# Esquema_V2_V1.net
KiCad netlist of a schematic drawn in Altium Designer
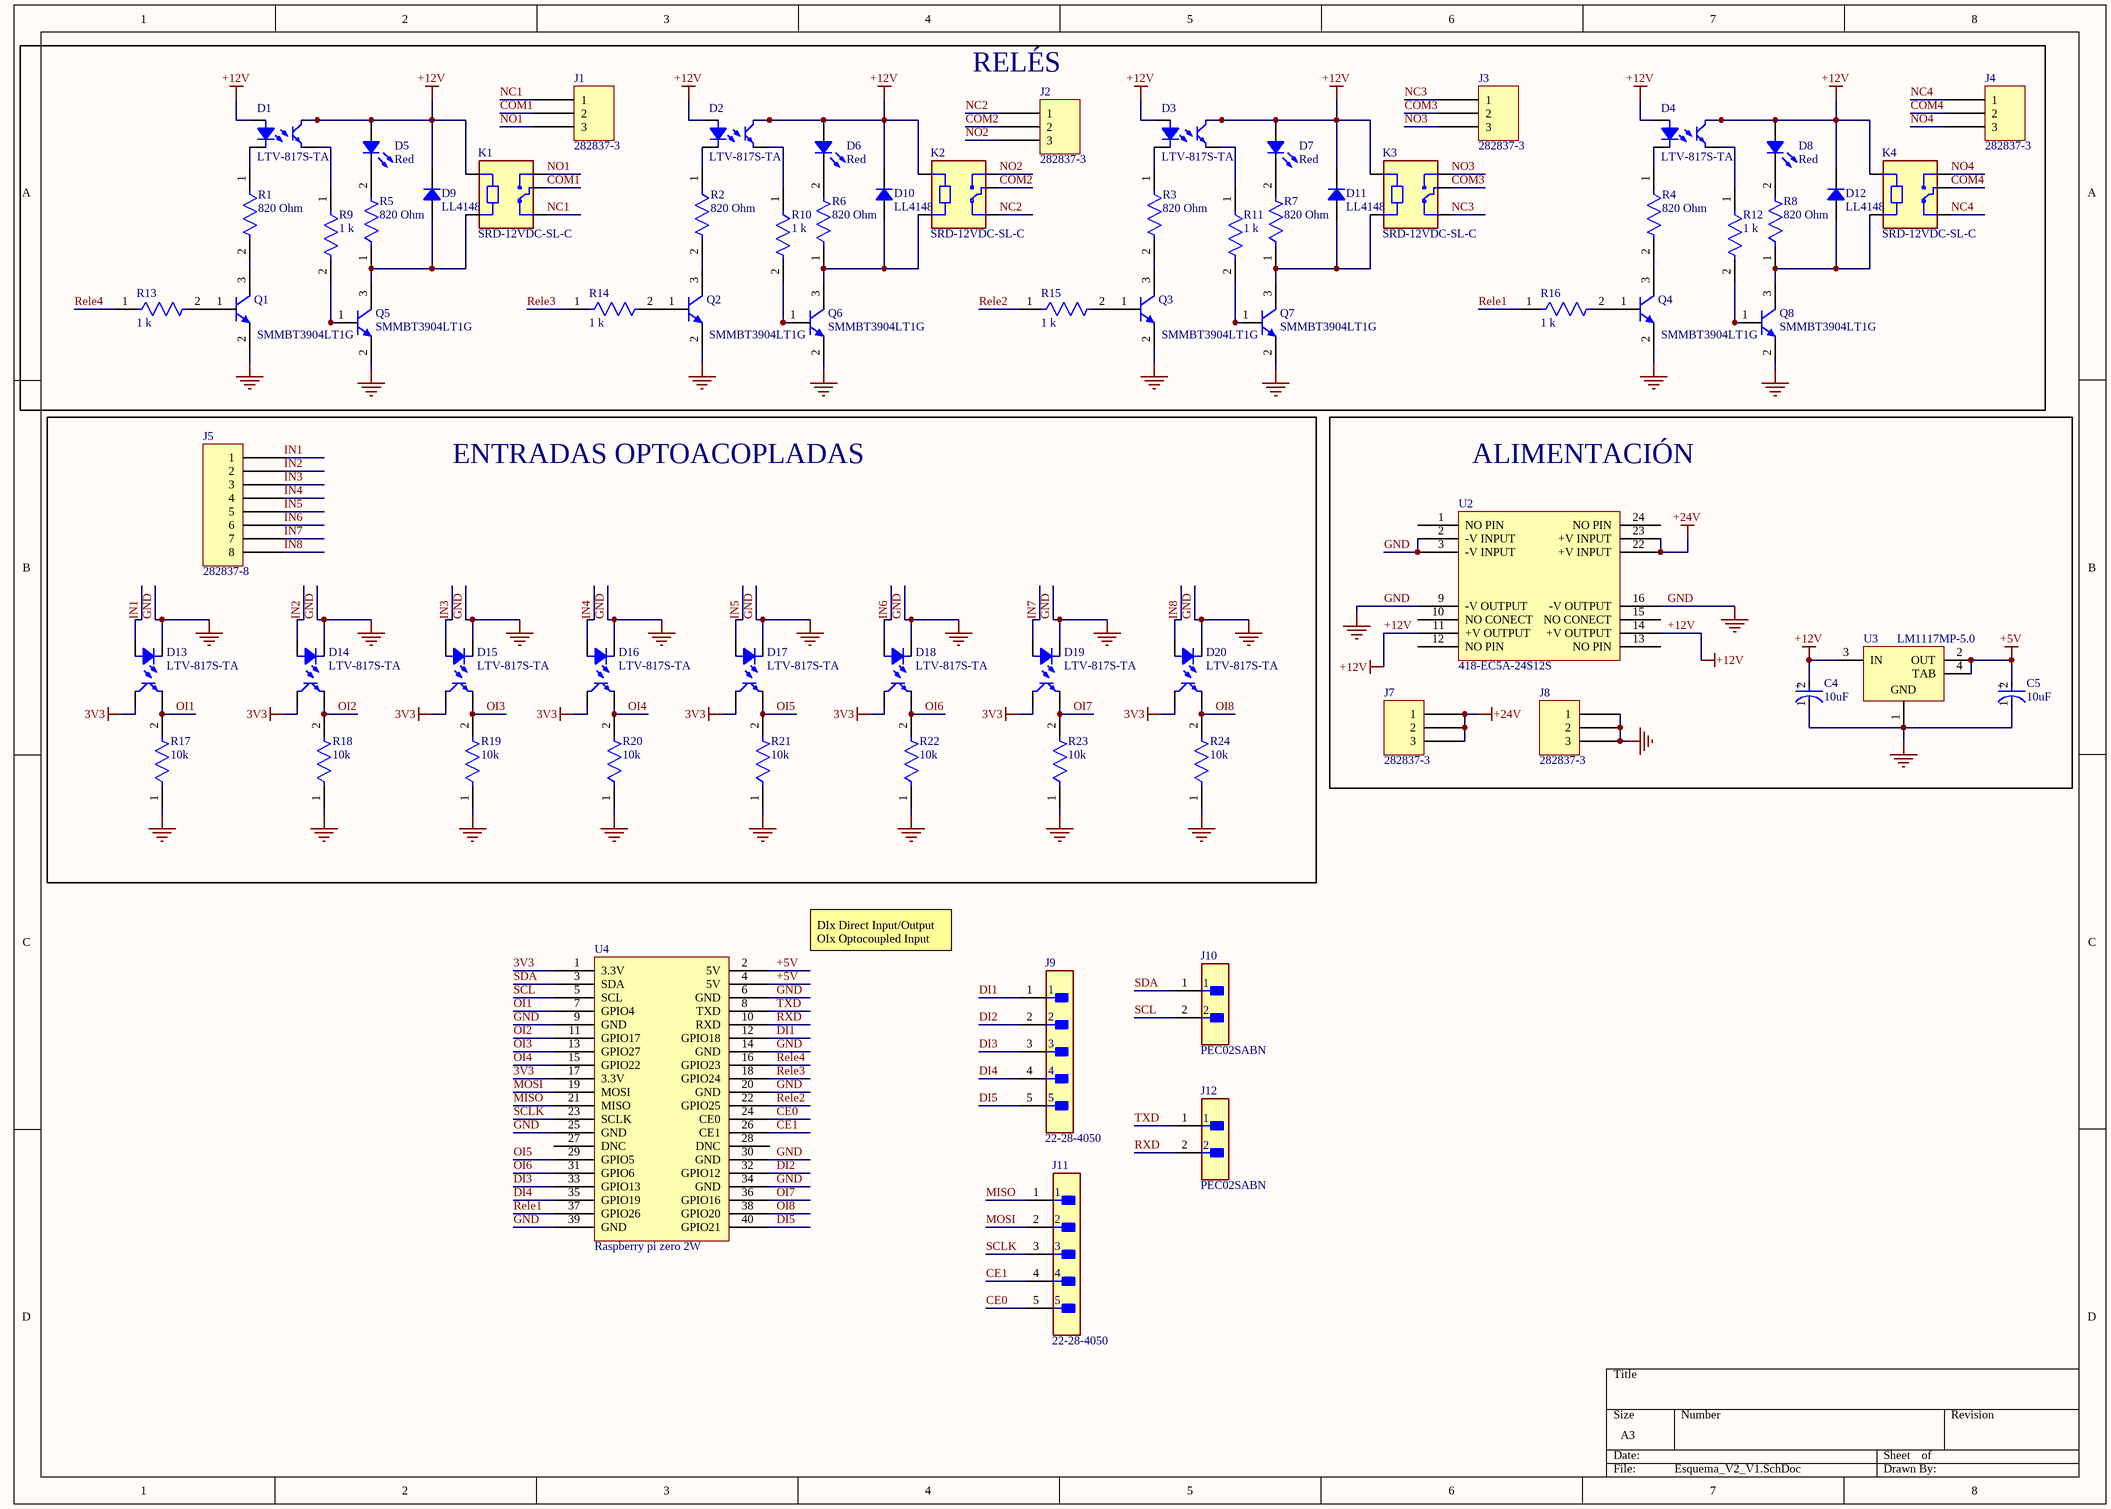
[diagram p0: Esquema_V2_V1.SchDoc]

(export (version "E")
  (design (tool "Eeschema 10.0.6"))
  (components
    (comp (ref "C4")
      (value "10uF")
      (footprint "FP-TAJA-MFG")
      (description "TAJA106M010RNJ 10uF 10V  ±20% 3Ω 1206  SMD Tantalum Capacitor")
      (fields (field (name "TOLERANCE") "20%") (field (name "VOLTAGE") "10V"))
      (libsource (lib "Altium Content Vault") (part "203bc49f2ac43e59fd269a8c329ed05"))
    )
    (comp (ref "C5")
      (value "10uF")
      (footprint "FP-TAJA-MFG")
      (description "TAJA106M010RNJ 10uF 10V  ±20% 3Ω 1206  SMD Tantalum Capacitor")
      (fields (field (name "TOLERANCE") "20%") (field (name "VOLTAGE") "10V"))
      (libsource (lib "Altium Content Vault") (part "203bc49f2ac43e59fd269a8c329ed05"))
    )
    (comp (ref "D1")
      (value "LTV-817S-TA")
      (footprint "LITEON LTV-817")
      (description "OPTOISOLATR 5KV TRANSISTOR 4-SMD")
      (fields (field (name "MANUFACTURER") "Lite-On Inc."))
      (libsource (lib "Celestial Altium Library - altium_library") (part "Optoisolator"))
    )
    (comp (ref "D2")
      (value "LTV-817S-TA")
      (footprint "LITEON LTV-817")
      (description "OPTOISOLATR 5KV TRANSISTOR 4-SMD")
      (fields (field (name "MANUFACTURER") "Lite-On Inc."))
      (libsource (lib "Celestial Altium Library - altium_library") (part "Optoisolator"))
    )
    (comp (ref "D3")
      (value "LTV-817S-TA")
      (footprint "LITEON LTV-817")
      (description "OPTOISOLATR 5KV TRANSISTOR 4-SMD")
      (fields (field (name "MANUFACTURER") "Lite-On Inc."))
      (libsource (lib "Celestial Altium Library - altium_library") (part "Optoisolator"))
    )
    (comp (ref "D4")
      (value "LTV-817S-TA")
      (footprint "LITEON LTV-817")
      (description "OPTOISOLATR 5KV TRANSISTOR 4-SMD")
      (fields (field (name "MANUFACTURER") "Lite-On Inc."))
      (libsource (lib "Celestial Altium Library - altium_library") (part "Optoisolator"))
    )
    (comp (ref "D5")
      (value "Red")
      (footprint "LED 1206_3216 RED")
      (description "LED RED CLEAR SMD")
      (fields (field (name "PART NUMBER") "LTST-C150KAKT") (field (name "MANUFACTURER") "Lite-On Inc."))
      (libsource (lib "Celestial Altium Library - altium_library") (part "LED"))
    )
    (comp (ref "D6")
      (value "Red")
      (footprint "LED 1206_3216 RED")
      (description "LED RED CLEAR SMD")
      (fields (field (name "PART NUMBER") "LTST-C150KAKT") (field (name "MANUFACTURER") "Lite-On Inc."))
      (libsource (lib "Celestial Altium Library - altium_library") (part "LED"))
    )
    (comp (ref "D7")
      (value "Red")
      (footprint "LED 1206_3216 RED")
      (description "LED RED CLEAR SMD")
      (fields (field (name "PART NUMBER") "LTST-C150KAKT") (field (name "MANUFACTURER") "Lite-On Inc."))
      (libsource (lib "Celestial Altium Library - altium_library") (part "LED"))
    )
    (comp (ref "D8")
      (value "Red")
      (footprint "LED 1206_3216 RED")
      (description "LED RED CLEAR SMD")
      (fields (field (name "PART NUMBER") "LTST-C150KAKT") (field (name "MANUFACTURER") "Lite-On Inc."))
      (libsource (lib "Celestial Altium Library - altium_library") (part "LED"))
    )
    (comp (ref "D9")
      (value "LL4148")
      (footprint "SOD-80 MiniMELF")
      (description "DIODE GEN PURP 100V 200MA SOD80")
      (fields (field (name "MANUFACTURER") "ON Semiconductor"))
      (libsource (lib "Celestial Altium Library - altium_library") (part "Diode"))
    )
    (comp (ref "D10")
      (value "LL4148")
      (footprint "SOD-80 MiniMELF")
      (description "DIODE GEN PURP 100V 200MA SOD80")
      (fields (field (name "MANUFACTURER") "ON Semiconductor"))
      (libsource (lib "Celestial Altium Library - altium_library") (part "Diode"))
    )
    (comp (ref "D11")
      (value "LL4148")
      (footprint "SOD-80 MiniMELF")
      (description "DIODE GEN PURP 100V 200MA SOD80")
      (fields (field (name "MANUFACTURER") "ON Semiconductor"))
      (libsource (lib "Celestial Altium Library - altium_library") (part "Diode"))
    )
    (comp (ref "D12")
      (value "LL4148")
      (footprint "SOD-80 MiniMELF")
      (description "DIODE GEN PURP 100V 200MA SOD80")
      (fields (field (name "MANUFACTURER") "ON Semiconductor"))
      (libsource (lib "Celestial Altium Library - altium_library") (part "Diode"))
    )
    (comp (ref "D13")
      (value "LTV-817S-TA")
      (footprint "LITEON LTV-817")
      (description "OPTOISOLATR 5KV TRANSISTOR 4-SMD")
      (fields (field (name "MANUFACTURER") "Lite-On Inc."))
      (libsource (lib "Celestial Altium Library - altium_library") (part "Optoisolator"))
    )
    (comp (ref "D14")
      (value "LTV-817S-TA")
      (footprint "LITEON LTV-817")
      (description "OPTOISOLATR 5KV TRANSISTOR 4-SMD")
      (fields (field (name "MANUFACTURER") "Lite-On Inc."))
      (libsource (lib "Celestial Altium Library - altium_library") (part "Optoisolator"))
    )
    (comp (ref "D15")
      (value "LTV-817S-TA")
      (footprint "LITEON LTV-817")
      (description "OPTOISOLATR 5KV TRANSISTOR 4-SMD")
      (fields (field (name "MANUFACTURER") "Lite-On Inc."))
      (libsource (lib "Celestial Altium Library - altium_library") (part "Optoisolator"))
    )
    (comp (ref "D16")
      (value "LTV-817S-TA")
      (footprint "LITEON LTV-817")
      (description "OPTOISOLATR 5KV TRANSISTOR 4-SMD")
      (fields (field (name "MANUFACTURER") "Lite-On Inc."))
      (libsource (lib "Celestial Altium Library - altium_library") (part "Optoisolator"))
    )
    (comp (ref "D17")
      (value "LTV-817S-TA")
      (footprint "LITEON LTV-817")
      (description "OPTOISOLATR 5KV TRANSISTOR 4-SMD")
      (fields (field (name "MANUFACTURER") "Lite-On Inc."))
      (libsource (lib "Celestial Altium Library - altium_library") (part "Optoisolator"))
    )
    (comp (ref "D18")
      (value "LTV-817S-TA")
      (footprint "LITEON LTV-817")
      (description "OPTOISOLATR 5KV TRANSISTOR 4-SMD")
      (fields (field (name "MANUFACTURER") "Lite-On Inc."))
      (libsource (lib "Celestial Altium Library - altium_library") (part "Optoisolator"))
    )
    (comp (ref "D19")
      (value "LTV-817S-TA")
      (footprint "LITEON LTV-817")
      (description "OPTOISOLATR 5KV TRANSISTOR 4-SMD")
      (fields (field (name "MANUFACTURER") "Lite-On Inc."))
      (libsource (lib "Celestial Altium Library - altium_library") (part "Optoisolator"))
    )
    (comp (ref "D20")
      (value "LTV-817S-TA")
      (footprint "LITEON LTV-817")
      (description "OPTOISOLATR 5KV TRANSISTOR 4-SMD")
      (fields (field (name "MANUFACTURER") "Lite-On Inc."))
      (libsource (lib "Celestial Altium Library - altium_library") (part "Optoisolator"))
    )
    (comp (ref "J1")
      (value "282837-3")
      (footprint "TE 282837-3")
      (description "TERM BLK 3P SIDE ENT 5.08MM PCB")
      (fields (field (name "MANUFACTURER") "TE Connectivity AMP Connectors") (field (name "VOLTAGE") "300 V"))
      (libsource (lib "Celestial Altium Library - altium_library") (part "3 Pin"))
    )
    (comp (ref "J2")
      (value "282837-3")
      (footprint "TE 282837-3")
      (description "TERM BLK 3P SIDE ENT 5.08MM PCB")
      (fields (field (name "MANUFACTURER") "TE Connectivity AMP Connectors") (field (name "VOLTAGE") "300 V"))
      (libsource (lib "Celestial Altium Library - altium_library") (part "3 Pin"))
    )
    (comp (ref "J3")
      (value "282837-3")
      (footprint "TE 282837-3")
      (description "TERM BLK 3P SIDE ENT 5.08MM PCB")
      (fields (field (name "MANUFACTURER") "TE Connectivity AMP Connectors") (field (name "VOLTAGE") "300 V"))
      (libsource (lib "Celestial Altium Library - altium_library") (part "3 Pin"))
    )
    (comp (ref "J4")
      (value "282837-3")
      (footprint "TE 282837-3")
      (description "TERM BLK 3P SIDE ENT 5.08MM PCB")
      (fields (field (name "MANUFACTURER") "TE Connectivity AMP Connectors") (field (name "VOLTAGE") "300 V"))
      (libsource (lib "Celestial Altium Library - altium_library") (part "3 Pin"))
    )
    (comp (ref "J5")
      (value "282837-8")
      (footprint "TE 282837-8")
      (description "TERM BLK 8P SIDE ENT 5.08MM PCB")
      (fields (field (name "MANUFACTURER") "TE Connectivity AMP Connectors") (field (name "VOLTAGE") "300 V"))
      (libsource (lib "Celestial Altium Library - altium_library") (part "8 Pin"))
    )
    (comp (ref "J7")
      (value "282837-3")
      (footprint "TE 282837-3")
      (description "TERM BLK 3P SIDE ENT 5.08MM PCB")
      (fields (field (name "MANUFACTURER") "TE Connectivity AMP Connectors") (field (name "VOLTAGE") "300 V"))
      (libsource (lib "") (part "3 Pin_1"))
    )
    (comp (ref "J8")
      (value "282837-3")
      (footprint "TE 282837-3")
      (description "TERM BLK 3P SIDE ENT 5.08MM PCB")
      (fields (field (name "MANUFACTURER") "TE Connectivity AMP Connectors") (field (name "VOLTAGE") "300 V"))
      (libsource (lib "") (part "3 Pin_1"))
    )
    (comp (ref "J9")
      (value "22-28-4050")
      (footprint "FP-22-28-4050-MFG")
      (libsource (lib "Altium Content Vault") (part "bf93c07fd2649a848d0ec8585582aab"))
    )
    (comp (ref "J10")
      (value "PEC02SABN")
      (footprint "FP-PEC02SABN-MFG")
      (description "CONN HEADER VERT 2POS 2.54MM")
      (libsource (lib "Altium Content Vault") (part "3bc925449376181038e59eaffc5286c"))
    )
    (comp (ref "J11")
      (value "22-28-4050")
      (footprint "FP-22-28-4050-MFG")
      (libsource (lib "Altium Content Vault") (part "bf93c07fd2649a848d0ec8585582aab"))
    )
    (comp (ref "J12")
      (value "PEC02SABN")
      (footprint "FP-PEC02SABN-MFG")
      (description "CONN HEADER VERT 2POS 2.54MM")
      (libsource (lib "Altium Content Vault") (part "3bc925449376181038e59eaffc5286c"))
    )
    (comp (ref "K1")
      (value "SRD-12VDC-SL-C")
      (footprint "RELAY_SRD-05VDC-SL-C")
      (fields (field (name "MF") "Songle Relay") (field (name "MP") "SRD-05VDC-SL-C"))
      (libsource (lib "SRD-05VDC-SL-C") (part "SRD-05VDC-SL-C"))
    )
    (comp (ref "K2")
      (value "SRD-12VDC-SL-C")
      (footprint "RELAY_SRD-05VDC-SL-C")
      (fields (field (name "MF") "Songle Relay") (field (name "MP") "SRD-05VDC-SL-C"))
      (libsource (lib "SRD-05VDC-SL-C") (part "SRD-05VDC-SL-C"))
    )
    (comp (ref "K3")
      (value "SRD-12VDC-SL-C")
      (footprint "RELAY_SRD-05VDC-SL-C")
      (fields (field (name "MF") "Songle Relay") (field (name "MP") "SRD-05VDC-SL-C"))
      (libsource (lib "SRD-05VDC-SL-C") (part "SRD-05VDC-SL-C"))
    )
    (comp (ref "K4")
      (value "SRD-12VDC-SL-C")
      (footprint "RELAY_SRD-05VDC-SL-C")
      (fields (field (name "MF") "Songle Relay") (field (name "MP") "SRD-05VDC-SL-C"))
      (libsource (lib "SRD-05VDC-SL-C") (part "SRD-05VDC-SL-C"))
    )
    (comp (ref "Q1")
      (value "SMMBT3904LT1G")
      (footprint "ONSC-SOT-23-3-318-08_V")
      (description "General Purpose Transistor, NPN Silicon, 3-Pin SOT-23, Pb-Free, Tape and Reel")
      (fields (field (name "MANUFACTURER") "On Semiconductor"))
      (libsource (lib "Altium Content Vault") (part "ONSC-NPN-B1E2C3-3"))
    )
    (comp (ref "Q2")
      (value "SMMBT3904LT1G")
      (footprint "ONSC-SOT-23-3-318-08_V")
      (description "General Purpose Transistor, NPN Silicon, 3-Pin SOT-23, Pb-Free, Tape and Reel")
      (fields (field (name "MANUFACTURER") "On Semiconductor"))
      (libsource (lib "Altium Content Vault") (part "ONSC-NPN-B1E2C3-3"))
    )
    (comp (ref "Q3")
      (value "SMMBT3904LT1G")
      (footprint "ONSC-SOT-23-3-318-08_V")
      (description "General Purpose Transistor, NPN Silicon, 3-Pin SOT-23, Pb-Free, Tape and Reel")
      (fields (field (name "MANUFACTURER") "On Semiconductor"))
      (libsource (lib "Altium Content Vault") (part "ONSC-NPN-B1E2C3-3"))
    )
    (comp (ref "Q4")
      (value "SMMBT3904LT1G")
      (footprint "ONSC-SOT-23-3-318-08_V")
      (description "General Purpose Transistor, NPN Silicon, 3-Pin SOT-23, Pb-Free, Tape and Reel")
      (fields (field (name "MANUFACTURER") "On Semiconductor"))
      (libsource (lib "Altium Content Vault") (part "ONSC-NPN-B1E2C3-3"))
    )
    (comp (ref "Q5")
      (value "SMMBT3904LT1G")
      (footprint "ONSC-SOT-23-3-318-08_V")
      (description "General Purpose Transistor, NPN Silicon, 3-Pin SOT-23, Pb-Free, Tape and Reel")
      (fields (field (name "MANUFACTURER") "On Semiconductor"))
      (libsource (lib "Altium Content Vault") (part "ONSC-NPN-B1E2C3-3"))
    )
    (comp (ref "Q6")
      (value "SMMBT3904LT1G")
      (footprint "ONSC-SOT-23-3-318-08_V")
      (description "General Purpose Transistor, NPN Silicon, 3-Pin SOT-23, Pb-Free, Tape and Reel")
      (fields (field (name "MANUFACTURER") "On Semiconductor"))
      (libsource (lib "Altium Content Vault") (part "ONSC-NPN-B1E2C3-3"))
    )
    (comp (ref "Q7")
      (value "SMMBT3904LT1G")
      (footprint "ONSC-SOT-23-3-318-08_V")
      (description "General Purpose Transistor, NPN Silicon, 3-Pin SOT-23, Pb-Free, Tape and Reel")
      (fields (field (name "MANUFACTURER") "On Semiconductor"))
      (libsource (lib "Altium Content Vault") (part "ONSC-NPN-B1E2C3-3"))
    )
    (comp (ref "Q8")
      (value "SMMBT3904LT1G")
      (footprint "ONSC-SOT-23-3-318-08_V")
      (description "General Purpose Transistor, NPN Silicon, 3-Pin SOT-23, Pb-Free, Tape and Reel")
      (fields (field (name "MANUFACTURER") "On Semiconductor"))
      (libsource (lib "Altium Content Vault") (part "ONSC-NPN-B1E2C3-3"))
    )
    (comp (ref "R1")
      (value "820 Ohm")
      (footprint "FP-CRCW0603-HPe3-MFG")
      (description "RES Thick Film, 820Ω, 1%, 0.33W, 100ppm/°C, 0603")
      (fields (field (name "TOLERANCE") "1%"))
      (libsource (lib "Altium Content Vault") (part "1029c3af85768c4190bb7ad29bc67b5"))
    )
    (comp (ref "R2")
      (value "820 Ohm")
      (footprint "FP-CRCW0603-HPe3-MFG")
      (description "RES Thick Film, 820Ω, 1%, 0.33W, 100ppm/°C, 0603")
      (fields (field (name "TOLERANCE") "1%"))
      (libsource (lib "Altium Content Vault") (part "1029c3af85768c4190bb7ad29bc67b5"))
    )
    (comp (ref "R3")
      (value "820 Ohm")
      (footprint "FP-CRCW0603-HPe3-MFG")
      (description "RES Thick Film, 820Ω, 1%, 0.33W, 100ppm/°C, 0603")
      (fields (field (name "TOLERANCE") "1%"))
      (libsource (lib "Altium Content Vault") (part "1029c3af85768c4190bb7ad29bc67b5"))
    )
    (comp (ref "R4")
      (value "820 Ohm")
      (footprint "FP-CRCW0603-HPe3-MFG")
      (description "RES Thick Film, 820Ω, 1%, 0.33W, 100ppm/°C, 0603")
      (fields (field (name "TOLERANCE") "1%"))
      (libsource (lib "Altium Content Vault") (part "1029c3af85768c4190bb7ad29bc67b5"))
    )
    (comp (ref "R5")
      (value "820 Ohm")
      (footprint "FP-CRCW0603-HPe3-MFG")
      (description "RES Thick Film, 820Ω, 1%, 0.33W, 100ppm/°C, 0603")
      (fields (field (name "TOLERANCE") "1%"))
      (libsource (lib "Altium Content Vault") (part "1029c3af85768c4190bb7ad29bc67b5"))
    )
    (comp (ref "R6")
      (value "820 Ohm")
      (footprint "FP-CRCW0603-HPe3-MFG")
      (description "RES Thick Film, 820Ω, 1%, 0.33W, 100ppm/°C, 0603")
      (fields (field (name "TOLERANCE") "1%"))
      (libsource (lib "Altium Content Vault") (part "1029c3af85768c4190bb7ad29bc67b5"))
    )
    (comp (ref "R7")
      (value "820 Ohm")
      (footprint "FP-CRCW0603-HPe3-MFG")
      (description "RES Thick Film, 820Ω, 1%, 0.33W, 100ppm/°C, 0603")
      (fields (field (name "TOLERANCE") "1%"))
      (libsource (lib "Altium Content Vault") (part "1029c3af85768c4190bb7ad29bc67b5"))
    )
    (comp (ref "R8")
      (value "820 Ohm")
      (footprint "FP-CRCW0603-HPe3-MFG")
      (description "RES Thick Film, 820Ω, 1%, 0.33W, 100ppm/°C, 0603")
      (fields (field (name "TOLERANCE") "1%"))
      (libsource (lib "Altium Content Vault") (part "1029c3af85768c4190bb7ad29bc67b5"))
    )
    (comp (ref "R9")
      (value "1 k")
      (footprint "FP-MCT0603-IPC_C")
      (description "MCT0603PD1001DP500 RES SMD 100 OHM 1% 1/8W 0603")
      (fields (field (name "TOLERANCE") "0.5%"))
      (libsource (lib "Altium Content Vault") (part "1029c3af85768c4190bb7ad29bc67b5"))
    )
    (comp (ref "R10")
      (value "1 k")
      (footprint "FP-MCT0603-IPC_C")
      (description "MCT0603PD1001DP500 RES SMD 100 OHM 1% 1/8W 0603")
      (fields (field (name "TOLERANCE") "0.5%"))
      (libsource (lib "Altium Content Vault") (part "1029c3af85768c4190bb7ad29bc67b5"))
    )
    (comp (ref "R11")
      (value "1 k")
      (footprint "FP-MCT0603-IPC_C")
      (description "MCT0603PD1001DP500 RES SMD 100 OHM 1% 1/8W 0603")
      (fields (field (name "TOLERANCE") "0.5%"))
      (libsource (lib "Altium Content Vault") (part "1029c3af85768c4190bb7ad29bc67b5"))
    )
    (comp (ref "R12")
      (value "1 k")
      (footprint "FP-MCT0603-IPC_C")
      (description "MCT0603PD1001DP500 RES SMD 100 OHM 1% 1/8W 0603")
      (fields (field (name "TOLERANCE") "0.5%"))
      (libsource (lib "Altium Content Vault") (part "1029c3af85768c4190bb7ad29bc67b5"))
    )
    (comp (ref "R13")
      (value "1 k")
      (footprint "FP-MCT0603-IPC_C")
      (description "MCT0603PD1001DP500 RES SMD 100 OHM 1% 1/8W 0603")
      (fields (field (name "TOLERANCE") "0.5%"))
      (libsource (lib "Altium Content Vault") (part "1029c3af85768c4190bb7ad29bc67b5"))
    )
    (comp (ref "R14")
      (value "1 k")
      (footprint "FP-MCT0603-IPC_C")
      (description "MCT0603PD1001DP500 RES SMD 100 OHM 1% 1/8W 0603")
      (fields (field (name "TOLERANCE") "0.5%"))
      (libsource (lib "Altium Content Vault") (part "1029c3af85768c4190bb7ad29bc67b5"))
    )
    (comp (ref "R15")
      (value "1 k")
      (footprint "FP-MCT0603-IPC_C")
      (description "MCT0603PD1001DP500 RES SMD 100 OHM 1% 1/8W 0603")
      (fields (field (name "TOLERANCE") "0.5%"))
      (libsource (lib "Altium Content Vault") (part "1029c3af85768c4190bb7ad29bc67b5"))
    )
    (comp (ref "R16")
      (value "1 k")
      (footprint "FP-MCT0603-IPC_C")
      (description "MCT0603PD1001DP500 RES SMD 100 OHM 1% 1/8W 0603")
      (fields (field (name "TOLERANCE") "0.5%"))
      (libsource (lib "Altium Content Vault") (part "1029c3af85768c4190bb7ad29bc67b5"))
    )
    (comp (ref "R17")
      (value "10k")
      (footprint "FP-MCT0603-IPC_B")
      (description "MCT0603MD1002BP100 RES SMD 10k OHM 1% 1/8W 0603")
      (fields (field (name "TOLERANCE") "0.1%"))
      (libsource (lib "Altium Content Vault") (part "1029c3af85768c4190bb7ad29bc67b5"))
    )
    (comp (ref "R18")
      (value "10k")
      (footprint "FP-MCT0603-IPC_B")
      (description "MCT0603MD1002BP100 RES SMD 10k OHM 1% 1/8W 0603")
      (fields (field (name "TOLERANCE") "0.1%"))
      (libsource (lib "Altium Content Vault") (part "1029c3af85768c4190bb7ad29bc67b5"))
    )
    (comp (ref "R19")
      (value "10k")
      (footprint "FP-MCT0603-IPC_B")
      (description "MCT0603MD1002BP100 RES SMD 10k OHM 1% 1/8W 0603")
      (fields (field (name "TOLERANCE") "0.1%"))
      (libsource (lib "Altium Content Vault") (part "1029c3af85768c4190bb7ad29bc67b5"))
    )
    (comp (ref "R20")
      (value "10k")
      (footprint "FP-MCT0603-IPC_B")
      (description "MCT0603MD1002BP100 RES SMD 10k OHM 1% 1/8W 0603")
      (fields (field (name "TOLERANCE") "0.1%"))
      (libsource (lib "Altium Content Vault") (part "1029c3af85768c4190bb7ad29bc67b5"))
    )
    (comp (ref "R21")
      (value "10k")
      (footprint "FP-MCT0603-IPC_B")
      (description "MCT0603MD1002BP100 RES SMD 10k OHM 1% 1/8W 0603")
      (fields (field (name "TOLERANCE") "0.1%"))
      (libsource (lib "Altium Content Vault") (part "1029c3af85768c4190bb7ad29bc67b5"))
    )
    (comp (ref "R22")
      (value "10k")
      (footprint "FP-MCT0603-IPC_B")
      (description "MCT0603MD1002BP100 RES SMD 10k OHM 1% 1/8W 0603")
      (fields (field (name "TOLERANCE") "0.1%"))
      (libsource (lib "Altium Content Vault") (part "1029c3af85768c4190bb7ad29bc67b5"))
    )
    (comp (ref "R23")
      (value "10k")
      (footprint "FP-MCT0603-IPC_B")
      (description "MCT0603MD1002BP100 RES SMD 10k OHM 1% 1/8W 0603")
      (fields (field (name "TOLERANCE") "0.1%"))
      (libsource (lib "Altium Content Vault") (part "1029c3af85768c4190bb7ad29bc67b5"))
    )
    (comp (ref "R24")
      (value "10k")
      (footprint "FP-MCT0603-IPC_B")
      (description "MCT0603MD1002BP100 RES SMD 10k OHM 1% 1/8W 0603")
      (fields (field (name "TOLERANCE") "0.1%"))
      (libsource (lib "Altium Content Vault") (part "1029c3af85768c4190bb7ad29bc67b5"))
    )
    (comp (ref "U2")
      (value "418-EC5A-24S12S")
      (footprint "418-EC5A-24S12S")
      (libsource (lib "Raspberry") (part "418-EC5A-24S12S"))
    )
    (comp (ref "U3")
      (value "LM1117MP-5.0")
      (footprint "MP04A_N")
      (description "800mA Low-Dropout Linear Regulator, 4-pin SOT-223")
      (fields (field (name "MANUFACTURER") "National Semiconductor"))
      (libsource (lib "Altium Content Vault") (part "PM-REG-LM1086-SOT4"))
    )
    (comp (ref "U4")
      (value "Raspberry pi zero 2W")
      (footprint "PCBComponent_1")
      (libsource (lib "Raspberry") (part "Raspberry pi zero 2W"))
    )
  )
  (nets
    (net (code "1") (name "+5V") (class "Default")
      (node (ref "C5") (pin "2") (pinfunction "A_2") (pintype "passive"))
      (node (ref "U3") (pin "2") (pinfunction "OUT_2") (pintype "power_in"))
      (node (ref "U3") (pin "4") (pinfunction "TAB_4") (pintype "power_in"))
      (node (ref "U4") (pin "2") (pinfunction "5V_2") (pintype "passive"))
      (node (ref "U4") (pin "4") (pinfunction "5V_4") (pintype "passive"))
    )
    (net (code "2") (name "+12V") (class "Default")
      (node (ref "C4") (pin "2") (pinfunction "A_2") (pintype "passive"))
      (node (ref "D1") (pin "1") (pinfunction "1_1") (pintype "passive"))
      (node (ref "D1") (pin "4") (pinfunction "4_4") (pintype "passive"))
      (node (ref "D10") (pin "2") (pinfunction "2_2") (pintype "passive"))
      (node (ref "D11") (pin "2") (pinfunction "2_2") (pintype "passive"))
      (node (ref "D12") (pin "2") (pinfunction "2_2") (pintype "passive"))
      (node (ref "D2") (pin "1") (pinfunction "1_1") (pintype "passive"))
      (node (ref "D2") (pin "4") (pinfunction "4_4") (pintype "passive"))
      (node (ref "D3") (pin "1") (pinfunction "1_1") (pintype "passive"))
      (node (ref "D3") (pin "4") (pinfunction "4_4") (pintype "passive"))
      (node (ref "D4") (pin "1") (pinfunction "1_1") (pintype "passive"))
      (node (ref "D4") (pin "4") (pinfunction "4_4") (pintype "passive"))
      (node (ref "D5") (pin "1") (pinfunction "1_1") (pintype "passive"))
      (node (ref "D6") (pin "1") (pinfunction "1_1") (pintype "passive"))
      (node (ref "D7") (pin "1") (pinfunction "1_1") (pintype "passive"))
      (node (ref "D8") (pin "1") (pinfunction "1_1") (pintype "passive"))
      (node (ref "D9") (pin "2") (pinfunction "2_2") (pintype "passive"))
      (node (ref "K1") (pin "A1") (pinfunction "A1_A1") (pintype "passive"))
      (node (ref "K2") (pin "A1") (pinfunction "A1_A1") (pintype "passive"))
      (node (ref "K3") (pin "A1") (pinfunction "A1_A1") (pintype "passive"))
      (node (ref "K4") (pin "A1") (pinfunction "A1_A1") (pintype "passive"))
      (node (ref "U2") (pin "11") (pinfunction "+V_OUTPUT_11") (pintype "passive"))
      (node (ref "U2") (pin "14") (pinfunction "+V_OUTPUT_14") (pintype "passive"))
      (node (ref "U3") (pin "3") (pinfunction "IN_3") (pintype "power_in"))
    )
    (net (code "3") (name "+24V") (class "Default")
      (node (ref "J7") (pin "1") (pinfunction "1_1") (pintype "passive"))
      (node (ref "J7") (pin "2") (pinfunction "2_2") (pintype "passive"))
      (node (ref "J7") (pin "3") (pinfunction "3_3") (pintype "passive"))
      (node (ref "U2") (pin "22") (pinfunction "+V_INPUT_22") (pintype "passive"))
      (node (ref "U2") (pin "23") (pinfunction "+V_INPUT_23") (pintype "passive"))
    )
    (net (code "4") (name "/CE0") (class "Default")
      (node (ref "J11") (pin "5") (pinfunction "5_5") (pintype "passive"))
      (node (ref "U4") (pin "24") (pinfunction "CE0_24") (pintype "passive"))
    )
    (net (code "5") (name "/CE1") (class "Default")
      (node (ref "J11") (pin "4") (pinfunction "4_4") (pintype "passive"))
      (node (ref "U4") (pin "26") (pinfunction "CE1_26") (pintype "passive"))
    )
    (net (code "6") (name "/COM1") (class "Default")
      (node (ref "J1") (pin "2") (pinfunction "2_2") (pintype "passive"))
      (node (ref "K1") (pin "COM") (pinfunction "COM_COM") (pintype "passive"))
    )
    (net (code "7") (name "/COM2") (class "Default")
      (node (ref "J2") (pin "2") (pinfunction "2_2") (pintype "passive"))
      (node (ref "K2") (pin "COM") (pinfunction "COM_COM") (pintype "passive"))
    )
    (net (code "8") (name "/COM3") (class "Default")
      (node (ref "J3") (pin "2") (pinfunction "2_2") (pintype "passive"))
      (node (ref "K3") (pin "COM") (pinfunction "COM_COM") (pintype "passive"))
    )
    (net (code "9") (name "/COM4") (class "Default")
      (node (ref "J4") (pin "2") (pinfunction "2_2") (pintype "passive"))
      (node (ref "K4") (pin "COM") (pinfunction "COM_COM") (pintype "passive"))
    )
    (net (code "10") (name "/DI1") (class "Default")
      (node (ref "J9") (pin "1") (pinfunction "1_1") (pintype "passive"))
      (node (ref "U4") (pin "12") (pinfunction "GPIO18_12") (pintype "passive"))
    )
    (net (code "11") (name "/DI2") (class "Default")
      (node (ref "J9") (pin "2") (pinfunction "2_2") (pintype "passive"))
      (node (ref "U4") (pin "32") (pinfunction "GPIO12_32") (pintype "passive"))
    )
    (net (code "12") (name "/DI3") (class "Default")
      (node (ref "J9") (pin "3") (pinfunction "3_3") (pintype "passive"))
      (node (ref "U4") (pin "33") (pinfunction "GPIO13_33") (pintype "passive"))
    )
    (net (code "13") (name "/DI4") (class "Default")
      (node (ref "J9") (pin "4") (pinfunction "4_4") (pintype "passive"))
      (node (ref "U4") (pin "35") (pinfunction "GPIO19_35") (pintype "passive"))
    )
    (net (code "14") (name "/DI5") (class "Default")
      (node (ref "J9") (pin "5") (pinfunction "5_5") (pintype "passive"))
      (node (ref "U4") (pin "40") (pinfunction "GPIO21_40") (pintype "passive"))
    )
    (net (code "15") (name "/IN1") (class "Default")
      (node (ref "D13") (pin "1") (pinfunction "1_1") (pintype "passive"))
      (node (ref "J5") (pin "1") (pinfunction "1_1") (pintype "passive"))
    )
    (net (code "16") (name "/IN2") (class "Default")
      (node (ref "D14") (pin "1") (pinfunction "1_1") (pintype "passive"))
      (node (ref "J5") (pin "2") (pinfunction "2_2") (pintype "passive"))
    )
    (net (code "17") (name "/IN3") (class "Default")
      (node (ref "D15") (pin "1") (pinfunction "1_1") (pintype "passive"))
      (node (ref "J5") (pin "3") (pinfunction "3_3") (pintype "passive"))
    )
    (net (code "18") (name "/IN4") (class "Default")
      (node (ref "D16") (pin "1") (pinfunction "1_1") (pintype "passive"))
      (node (ref "J5") (pin "4") (pinfunction "4_4") (pintype "passive"))
    )
    (net (code "19") (name "/IN5") (class "Default")
      (node (ref "D17") (pin "1") (pinfunction "1_1") (pintype "passive"))
      (node (ref "J5") (pin "5") (pinfunction "5_5") (pintype "passive"))
    )
    (net (code "20") (name "/IN6") (class "Default")
      (node (ref "D18") (pin "1") (pinfunction "1_1") (pintype "passive"))
      (node (ref "J5") (pin "6") (pinfunction "6_6") (pintype "passive"))
    )
    (net (code "21") (name "/IN7") (class "Default")
      (node (ref "D19") (pin "1") (pinfunction "1_1") (pintype "passive"))
      (node (ref "J5") (pin "7") (pinfunction "7_7") (pintype "passive"))
    )
    (net (code "22") (name "/IN8") (class "Default")
      (node (ref "D20") (pin "1") (pinfunction "1_1") (pintype "passive"))
      (node (ref "J5") (pin "8") (pinfunction "8_8") (pintype "passive"))
    )
    (net (code "23") (name "/MISO") (class "Default")
      (node (ref "J11") (pin "1") (pinfunction "1_1") (pintype "passive"))
      (node (ref "U4") (pin "21") (pinfunction "MISO_21") (pintype "passive"))
    )
    (net (code "24") (name "/MOSI") (class "Default")
      (node (ref "J11") (pin "2") (pinfunction "2_2") (pintype "passive"))
      (node (ref "U4") (pin "19") (pinfunction "MOSI_19") (pintype "passive"))
    )
    (net (code "25") (name "/NC1") (class "Default")
      (node (ref "J1") (pin "1") (pinfunction "1_1") (pintype "passive"))
      (node (ref "K1") (pin "NC") (pinfunction "NC_NC") (pintype "passive"))
    )
    (net (code "26") (name "/NC2") (class "Default")
      (node (ref "J2") (pin "1") (pinfunction "1_1") (pintype "passive"))
      (node (ref "K2") (pin "NC") (pinfunction "NC_NC") (pintype "passive"))
    )
    (net (code "27") (name "/NC3") (class "Default")
      (node (ref "J3") (pin "1") (pinfunction "1_1") (pintype "passive"))
      (node (ref "K3") (pin "NC") (pinfunction "NC_NC") (pintype "passive"))
    )
    (net (code "28") (name "/NC4") (class "Default")
      (node (ref "J4") (pin "1") (pinfunction "1_1") (pintype "passive"))
      (node (ref "K4") (pin "NC") (pinfunction "NC_NC") (pintype "passive"))
    )
    (net (code "29") (name "/NO1") (class "Default")
      (node (ref "J1") (pin "3") (pinfunction "3_3") (pintype "passive"))
      (node (ref "K1") (pin "NO") (pinfunction "NO_NO") (pintype "passive"))
    )
    (net (code "30") (name "/NO2") (class "Default")
      (node (ref "J2") (pin "3") (pinfunction "3_3") (pintype "passive"))
      (node (ref "K2") (pin "NO") (pinfunction "NO_NO") (pintype "passive"))
    )
    (net (code "31") (name "/NO3") (class "Default")
      (node (ref "J3") (pin "3") (pinfunction "3_3") (pintype "passive"))
      (node (ref "K3") (pin "NO") (pinfunction "NO_NO") (pintype "passive"))
    )
    (net (code "32") (name "/NO4") (class "Default")
      (node (ref "J4") (pin "3") (pinfunction "3_3") (pintype "passive"))
      (node (ref "K4") (pin "NO") (pinfunction "NO_NO") (pintype "passive"))
    )
    (net (code "33") (name "/OI1") (class "Default")
      (node (ref "D13") (pin "3") (pinfunction "3_3") (pintype "passive"))
      (node (ref "R17") (pin "2") (pinfunction "2_2") (pintype "passive"))
      (node (ref "U4") (pin "7") (pinfunction "GPIO4_7") (pintype "passive"))
    )
    (net (code "34") (name "/OI2") (class "Default")
      (node (ref "D14") (pin "3") (pinfunction "3_3") (pintype "passive"))
      (node (ref "R18") (pin "2") (pinfunction "2_2") (pintype "passive"))
      (node (ref "U4") (pin "11") (pinfunction "GPIO17_11") (pintype "passive"))
    )
    (net (code "35") (name "/OI3") (class "Default")
      (node (ref "D15") (pin "3") (pinfunction "3_3") (pintype "passive"))
      (node (ref "R19") (pin "2") (pinfunction "2_2") (pintype "passive"))
      (node (ref "U4") (pin "13") (pinfunction "GPIO27_13") (pintype "passive"))
    )
    (net (code "36") (name "/OI4") (class "Default")
      (node (ref "D16") (pin "3") (pinfunction "3_3") (pintype "passive"))
      (node (ref "R20") (pin "2") (pinfunction "2_2") (pintype "passive"))
      (node (ref "U4") (pin "15") (pinfunction "GPIO22_15") (pintype "passive"))
    )
    (net (code "37") (name "/OI5") (class "Default")
      (node (ref "D17") (pin "3") (pinfunction "3_3") (pintype "passive"))
      (node (ref "R21") (pin "2") (pinfunction "2_2") (pintype "passive"))
      (node (ref "U4") (pin "29") (pinfunction "GPIO5_29") (pintype "passive"))
    )
    (net (code "38") (name "/OI6") (class "Default")
      (node (ref "D18") (pin "3") (pinfunction "3_3") (pintype "passive"))
      (node (ref "R22") (pin "2") (pinfunction "2_2") (pintype "passive"))
      (node (ref "U4") (pin "31") (pinfunction "GPIO6_31") (pintype "passive"))
    )
    (net (code "39") (name "/OI7") (class "Default")
      (node (ref "D19") (pin "3") (pinfunction "3_3") (pintype "passive"))
      (node (ref "R23") (pin "2") (pinfunction "2_2") (pintype "passive"))
      (node (ref "U4") (pin "36") (pinfunction "GPIO16_36") (pintype "passive"))
    )
    (net (code "40") (name "/OI8") (class "Default")
      (node (ref "D20") (pin "3") (pinfunction "3_3") (pintype "passive"))
      (node (ref "R24") (pin "2") (pinfunction "2_2") (pintype "passive"))
      (node (ref "U4") (pin "38") (pinfunction "GPIO20_38") (pintype "passive"))
    )
    (net (code "41") (name "/RXD") (class "Default")
      (node (ref "J12") (pin "2") (pinfunction "2_2") (pintype "passive"))
      (node (ref "U4") (pin "10") (pinfunction "RXD_10") (pintype "passive"))
    )
    (net (code "42") (name "/Rele1") (class "Default")
      (node (ref "R16") (pin "1") (pinfunction "1_1") (pintype "passive"))
      (node (ref "U4") (pin "37") (pinfunction "GPIO26_37") (pintype "passive"))
    )
    (net (code "43") (name "/Rele2") (class "Default")
      (node (ref "R15") (pin "1") (pinfunction "1_1") (pintype "passive"))
      (node (ref "U4") (pin "22") (pinfunction "GPIO25_22") (pintype "passive"))
    )
    (net (code "44") (name "/Rele3") (class "Default")
      (node (ref "R14") (pin "1") (pinfunction "1_1") (pintype "passive"))
      (node (ref "U4") (pin "18") (pinfunction "GPIO24_18") (pintype "passive"))
    )
    (net (code "45") (name "/Rele4") (class "Default")
      (node (ref "R13") (pin "1") (pinfunction "1_1") (pintype "passive"))
      (node (ref "U4") (pin "16") (pinfunction "GPIO23_16") (pintype "passive"))
    )
    (net (code "46") (name "/SCL") (class "Default")
      (node (ref "J10") (pin "2") (pinfunction "2_2") (pintype "passive"))
      (node (ref "U4") (pin "5") (pinfunction "SCL_5") (pintype "passive"))
    )
    (net (code "47") (name "/SCLK") (class "Default")
      (node (ref "J11") (pin "3") (pinfunction "3_3") (pintype "passive"))
      (node (ref "U4") (pin "23") (pinfunction "SCLK_23") (pintype "passive"))
    )
    (net (code "48") (name "/SDA") (class "Default")
      (node (ref "J10") (pin "1") (pinfunction "1_1") (pintype "passive"))
      (node (ref "U4") (pin "3") (pinfunction "SDA_3") (pintype "passive"))
    )
    (net (code "49") (name "/TXD") (class "Default")
      (node (ref "J12") (pin "1") (pinfunction "1_1") (pintype "passive"))
      (node (ref "U4") (pin "8") (pinfunction "TXD_8") (pintype "passive"))
    )
    (net (code "50") (name "3V3") (class "Default")
      (node (ref "D13") (pin "4") (pinfunction "4_4") (pintype "passive"))
      (node (ref "D14") (pin "4") (pinfunction "4_4") (pintype "passive"))
      (node (ref "D15") (pin "4") (pinfunction "4_4") (pintype "passive"))
      (node (ref "D16") (pin "4") (pinfunction "4_4") (pintype "passive"))
      (node (ref "D17") (pin "4") (pinfunction "4_4") (pintype "passive"))
      (node (ref "D18") (pin "4") (pinfunction "4_4") (pintype "passive"))
      (node (ref "D19") (pin "4") (pinfunction "4_4") (pintype "passive"))
      (node (ref "D20") (pin "4") (pinfunction "4_4") (pintype "passive"))
      (node (ref "U4") (pin "1") (pinfunction "3.3V_1") (pintype "passive"))
      (node (ref "U4") (pin "17") (pinfunction "3.3V_17") (pintype "passive"))
    )
    (net (code "51") (name "GND") (class "Default")
      (node (ref "C4") (pin "1") (pinfunction "C_1") (pintype "passive"))
      (node (ref "C5") (pin "1") (pinfunction "C_1") (pintype "passive"))
      (node (ref "D13") (pin "2") (pinfunction "2_2") (pintype "passive"))
      (node (ref "D14") (pin "2") (pinfunction "2_2") (pintype "passive"))
      (node (ref "D15") (pin "2") (pinfunction "2_2") (pintype "passive"))
      (node (ref "D16") (pin "2") (pinfunction "2_2") (pintype "passive"))
      (node (ref "D17") (pin "2") (pinfunction "2_2") (pintype "passive"))
      (node (ref "D18") (pin "2") (pinfunction "2_2") (pintype "passive"))
      (node (ref "D19") (pin "2") (pinfunction "2_2") (pintype "passive"))
      (node (ref "D20") (pin "2") (pinfunction "2_2") (pintype "passive"))
      (node (ref "J8") (pin "1") (pinfunction "1_1") (pintype "passive"))
      (node (ref "J8") (pin "2") (pinfunction "2_2") (pintype "passive"))
      (node (ref "J8") (pin "3") (pinfunction "3_3") (pintype "passive"))
      (node (ref "Q1") (pin "2") (pinfunction "E_2") (pintype "passive"))
      (node (ref "Q2") (pin "2") (pinfunction "E_2") (pintype "passive"))
      (node (ref "Q3") (pin "2") (pinfunction "E_2") (pintype "passive"))
      (node (ref "Q4") (pin "2") (pinfunction "E_2") (pintype "passive"))
      (node (ref "Q5") (pin "2") (pinfunction "E_2") (pintype "passive"))
      (node (ref "Q6") (pin "2") (pinfunction "E_2") (pintype "passive"))
      (node (ref "Q7") (pin "2") (pinfunction "E_2") (pintype "passive"))
      (node (ref "Q8") (pin "2") (pinfunction "E_2") (pintype "passive"))
      (node (ref "R17") (pin "1") (pinfunction "1_1") (pintype "passive"))
      (node (ref "R18") (pin "1") (pinfunction "1_1") (pintype "passive"))
      (node (ref "R19") (pin "1") (pinfunction "1_1") (pintype "passive"))
      (node (ref "R20") (pin "1") (pinfunction "1_1") (pintype "passive"))
      (node (ref "R21") (pin "1") (pinfunction "1_1") (pintype "passive"))
      (node (ref "R22") (pin "1") (pinfunction "1_1") (pintype "passive"))
      (node (ref "R23") (pin "1") (pinfunction "1_1") (pintype "passive"))
      (node (ref "R24") (pin "1") (pinfunction "1_1") (pintype "passive"))
      (node (ref "U2") (pin "16") (pinfunction "-V_OUTPUT_16") (pintype "passive"))
      (node (ref "U2") (pin "2") (pinfunction "-V_INPUT_2") (pintype "passive"))
      (node (ref "U2") (pin "3") (pinfunction "-V_INPUT_3") (pintype "passive"))
      (node (ref "U2") (pin "9") (pinfunction "-V_OUTPUT_9") (pintype "passive"))
      (node (ref "U3") (pin "1") (pinfunction "GND_1") (pintype "power_in"))
      (node (ref "U4") (pin "14") (pinfunction "GND_14") (pintype "passive"))
      (node (ref "U4") (pin "20") (pinfunction "GND_20") (pintype "passive"))
      (node (ref "U4") (pin "25") (pinfunction "GND_25") (pintype "passive"))
      (node (ref "U4") (pin "30") (pinfunction "GND_30") (pintype "passive"))
      (node (ref "U4") (pin "34") (pinfunction "GND_34") (pintype "passive"))
      (node (ref "U4") (pin "39") (pinfunction "GND_39") (pintype "passive"))
      (node (ref "U4") (pin "6") (pinfunction "GND_6") (pintype "passive"))
      (node (ref "U4") (pin "9") (pinfunction "GND_9") (pintype "passive"))
    )
    (net (code "52") (name "Net-(D1-Pad2)") (class "Default")
      (node (ref "D1") (pin "2") (pinfunction "2_2") (pintype "passive"))
      (node (ref "R1") (pin "1") (pinfunction "1_1") (pintype "passive"))
    )
    (net (code "53") (name "Net-(D1-Pad3)") (class "Default")
      (node (ref "D1") (pin "3") (pinfunction "3_3") (pintype "passive"))
      (node (ref "R9") (pin "1") (pinfunction "1_1") (pintype "passive"))
    )
    (net (code "54") (name "Net-(D2-Pad2)") (class "Default")
      (node (ref "D2") (pin "2") (pinfunction "2_2") (pintype "passive"))
      (node (ref "R2") (pin "1") (pinfunction "1_1") (pintype "passive"))
    )
    (net (code "55") (name "Net-(D2-Pad3)") (class "Default")
      (node (ref "D2") (pin "3") (pinfunction "3_3") (pintype "passive"))
      (node (ref "R10") (pin "1") (pinfunction "1_1") (pintype "passive"))
    )
    (net (code "56") (name "Net-(D3-Pad2)") (class "Default")
      (node (ref "D3") (pin "2") (pinfunction "2_2") (pintype "passive"))
      (node (ref "R3") (pin "1") (pinfunction "1_1") (pintype "passive"))
    )
    (net (code "57") (name "Net-(D3-Pad3)") (class "Default")
      (node (ref "D3") (pin "3") (pinfunction "3_3") (pintype "passive"))
      (node (ref "R11") (pin "1") (pinfunction "1_1") (pintype "passive"))
    )
    (net (code "58") (name "Net-(D4-Pad2)") (class "Default")
      (node (ref "D4") (pin "2") (pinfunction "2_2") (pintype "passive"))
      (node (ref "R4") (pin "1") (pinfunction "1_1") (pintype "passive"))
    )
    (net (code "59") (name "Net-(D4-Pad3)") (class "Default")
      (node (ref "D4") (pin "3") (pinfunction "3_3") (pintype "passive"))
      (node (ref "R12") (pin "1") (pinfunction "1_1") (pintype "passive"))
    )
    (net (code "60") (name "Net-(D5-Pad2)") (class "Default")
      (node (ref "D5") (pin "2") (pinfunction "2_2") (pintype "passive"))
      (node (ref "R5") (pin "2") (pinfunction "2_2") (pintype "passive"))
    )
    (net (code "61") (name "Net-(D6-Pad2)") (class "Default")
      (node (ref "D6") (pin "2") (pinfunction "2_2") (pintype "passive"))
      (node (ref "R6") (pin "2") (pinfunction "2_2") (pintype "passive"))
    )
    (net (code "62") (name "Net-(D7-Pad2)") (class "Default")
      (node (ref "D7") (pin "2") (pinfunction "2_2") (pintype "passive"))
      (node (ref "R7") (pin "2") (pinfunction "2_2") (pintype "passive"))
    )
    (net (code "63") (name "Net-(D8-Pad2)") (class "Default")
      (node (ref "D8") (pin "2") (pinfunction "2_2") (pintype "passive"))
      (node (ref "R8") (pin "2") (pinfunction "2_2") (pintype "passive"))
    )
    (net (code "64") (name "Net-(Q1-B)") (class "Default")
      (node (ref "Q1") (pin "1") (pinfunction "B_1") (pintype "passive"))
      (node (ref "R13") (pin "2") (pinfunction "2_2") (pintype "passive"))
    )
    (net (code "65") (name "Net-(Q1-C)") (class "Default")
      (node (ref "Q1") (pin "3") (pinfunction "C_3") (pintype "passive"))
      (node (ref "R1") (pin "2") (pinfunction "2_2") (pintype "passive"))
    )
    (net (code "66") (name "Net-(Q2-B)") (class "Default")
      (node (ref "Q2") (pin "1") (pinfunction "B_1") (pintype "passive"))
      (node (ref "R14") (pin "2") (pinfunction "2_2") (pintype "passive"))
    )
    (net (code "67") (name "Net-(Q2-C)") (class "Default")
      (node (ref "Q2") (pin "3") (pinfunction "C_3") (pintype "passive"))
      (node (ref "R2") (pin "2") (pinfunction "2_2") (pintype "passive"))
    )
    (net (code "68") (name "Net-(Q3-B)") (class "Default")
      (node (ref "Q3") (pin "1") (pinfunction "B_1") (pintype "passive"))
      (node (ref "R15") (pin "2") (pinfunction "2_2") (pintype "passive"))
    )
    (net (code "69") (name "Net-(Q3-C)") (class "Default")
      (node (ref "Q3") (pin "3") (pinfunction "C_3") (pintype "passive"))
      (node (ref "R3") (pin "2") (pinfunction "2_2") (pintype "passive"))
    )
    (net (code "70") (name "Net-(Q4-B)") (class "Default")
      (node (ref "Q4") (pin "1") (pinfunction "B_1") (pintype "passive"))
      (node (ref "R16") (pin "2") (pinfunction "2_2") (pintype "passive"))
    )
    (net (code "71") (name "Net-(Q4-C)") (class "Default")
      (node (ref "Q4") (pin "3") (pinfunction "C_3") (pintype "passive"))
      (node (ref "R4") (pin "2") (pinfunction "2_2") (pintype "passive"))
    )
    (net (code "72") (name "Net-(Q5-B)") (class "Default")
      (node (ref "Q5") (pin "1") (pinfunction "B_1") (pintype "passive"))
      (node (ref "R9") (pin "2") (pinfunction "2_2") (pintype "passive"))
    )
    (net (code "73") (name "Net-(Q5-C)") (class "Default")
      (node (ref "D9") (pin "1") (pinfunction "1_1") (pintype "passive"))
      (node (ref "K1") (pin "A2") (pinfunction "A2_A2") (pintype "passive"))
      (node (ref "Q5") (pin "3") (pinfunction "C_3") (pintype "passive"))
      (node (ref "R5") (pin "1") (pinfunction "1_1") (pintype "passive"))
    )
    (net (code "74") (name "Net-(Q6-B)") (class "Default")
      (node (ref "Q6") (pin "1") (pinfunction "B_1") (pintype "passive"))
      (node (ref "R10") (pin "2") (pinfunction "2_2") (pintype "passive"))
    )
    (net (code "75") (name "Net-(Q6-C)") (class "Default")
      (node (ref "D10") (pin "1") (pinfunction "1_1") (pintype "passive"))
      (node (ref "K2") (pin "A2") (pinfunction "A2_A2") (pintype "passive"))
      (node (ref "Q6") (pin "3") (pinfunction "C_3") (pintype "passive"))
      (node (ref "R6") (pin "1") (pinfunction "1_1") (pintype "passive"))
    )
    (net (code "76") (name "Net-(Q7-B)") (class "Default")
      (node (ref "Q7") (pin "1") (pinfunction "B_1") (pintype "passive"))
      (node (ref "R11") (pin "2") (pinfunction "2_2") (pintype "passive"))
    )
    (net (code "77") (name "Net-(Q7-C)") (class "Default")
      (node (ref "D11") (pin "1") (pinfunction "1_1") (pintype "passive"))
      (node (ref "K3") (pin "A2") (pinfunction "A2_A2") (pintype "passive"))
      (node (ref "Q7") (pin "3") (pinfunction "C_3") (pintype "passive"))
      (node (ref "R7") (pin "1") (pinfunction "1_1") (pintype "passive"))
    )
    (net (code "78") (name "Net-(Q8-B)") (class "Default")
      (node (ref "Q8") (pin "1") (pinfunction "B_1") (pintype "passive"))
      (node (ref "R12") (pin "2") (pinfunction "2_2") (pintype "passive"))
    )
    (net (code "79") (name "Net-(Q8-C)") (class "Default")
      (node (ref "D12") (pin "1") (pinfunction "1_1") (pintype "passive"))
      (node (ref "K4") (pin "A2") (pinfunction "A2_A2") (pintype "passive"))
      (node (ref "Q8") (pin "3") (pinfunction "C_3") (pintype "passive"))
      (node (ref "R8") (pin "1") (pinfunction "1_1") (pintype "passive"))
    )
    (net (code "80") (name "unconnected-(U2-NO_CONECT-Pad10)") (class "Default")
      (node (ref "U2") (pin "10") (pinfunction "NO_CONECT_10") (pintype "passive"))
    )
    (net (code "81") (name "unconnected-(U2-NO_CONECT-Pad15)") (class "Default")
      (node (ref "U2") (pin "15") (pinfunction "NO_CONECT_15") (pintype "passive"))
    )
    (net (code "82") (name "unconnected-(U2-NO_PIN-Pad1)") (class "Default")
      (node (ref "U2") (pin "1") (pinfunction "NO_PIN_1") (pintype "passive"))
    )
    (net (code "83") (name "unconnected-(U2-NO_PIN-Pad12)") (class "Default")
      (node (ref "U2") (pin "12") (pinfunction "NO_PIN_12") (pintype "passive"))
    )
    (net (code "84") (name "unconnected-(U2-NO_PIN-Pad13)") (class "Default")
      (node (ref "U2") (pin "13") (pinfunction "NO_PIN_13") (pintype "passive"))
    )
    (net (code "85") (name "unconnected-(U2-NO_PIN-Pad24)") (class "Default")
      (node (ref "U2") (pin "24") (pinfunction "NO_PIN_24") (pintype "passive"))
    )
    (net (code "86") (name "unconnected-(U4-DNC-Pad27)") (class "Default")
      (node (ref "U4") (pin "27") (pinfunction "DNC_27") (pintype "passive"))
    )
    (net (code "87") (name "unconnected-(U4-DNC-Pad28)") (class "Default")
      (node (ref "U4") (pin "28") (pinfunction "DNC_28") (pintype "passive"))
    )
  )
)
